# fda.net
KiCad netlist of a schematic drawn in Altium Designer
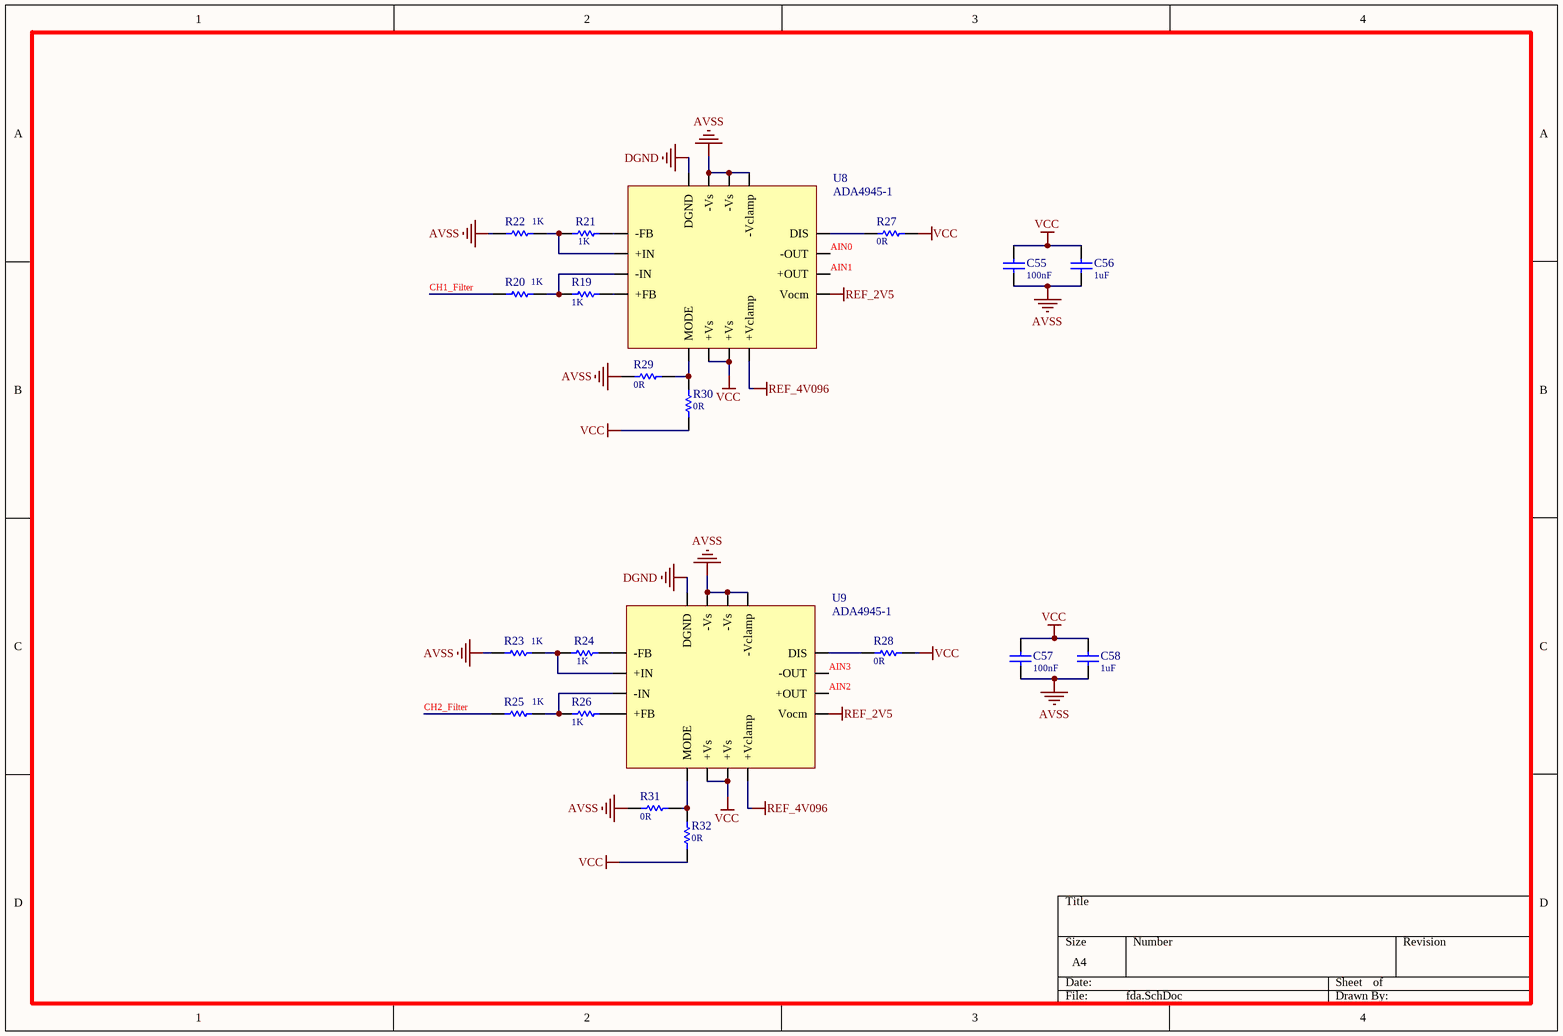
[diagram p0: fda.SchDoc]

(export (version "E")
  (design (tool "Eeschema 10.0.6"))
  (components
    (comp (ref "C55")
      (value "100nF")
      (footprint "C0603-L")
      (description "贴片瓷片电容")
      (fields (field (name "Comment") "Cap-S"))
      (libsource (lib "XuZhe") (part "Cap-S"))
    )
    (comp (ref "C56")
      (value "1uF")
      (footprint "C0603-L")
      (description "贴片瓷片电容")
      (fields (field (name "Comment") "Cap-S"))
      (libsource (lib "XuZhe") (part "Cap-S"))
    )
    (comp (ref "C57")
      (value "100nF")
      (footprint "C0603-L")
      (description "贴片瓷片电容")
      (fields (field (name "Comment") "Cap-S"))
      (libsource (lib "XuZhe") (part "Cap-S"))
    )
    (comp (ref "C58")
      (value "1uF")
      (footprint "C0603-L")
      (description "贴片瓷片电容")
      (fields (field (name "Comment") "Cap-S"))
      (libsource (lib "XuZhe") (part "Cap-S"))
    )
    (comp (ref "R19")
      (value "1K")
      (footprint "R0603-L")
      (description "贴片电阻")
      (fields (field (name "Comment") "R"))
      (libsource (lib "XuZhe") (part "Res"))
    )
    (comp (ref "R20")
      (value "1K")
      (footprint "R0603-L")
      (description "贴片电阻")
      (fields (field (name "Comment") "R"))
      (libsource (lib "XuZhe") (part "Res"))
    )
    (comp (ref "R21")
      (value "1K")
      (footprint "R0603-L")
      (description "贴片电阻")
      (fields (field (name "Comment") "R"))
      (libsource (lib "XuZhe") (part "Res"))
    )
    (comp (ref "R22")
      (value "1K")
      (footprint "R0603-L")
      (description "贴片电阻")
      (fields (field (name "Comment") "R"))
      (libsource (lib "XuZhe") (part "Res"))
    )
    (comp (ref "R23")
      (value "1K")
      (footprint "R0603-L")
      (description "贴片电阻")
      (fields (field (name "Comment") "R"))
      (libsource (lib "XuZhe") (part "Res"))
    )
    (comp (ref "R24")
      (value "1K")
      (footprint "R0603-L")
      (description "贴片电阻")
      (fields (field (name "Comment") "R"))
      (libsource (lib "XuZhe") (part "Res"))
    )
    (comp (ref "R25")
      (value "1K")
      (footprint "R0603-L")
      (description "贴片电阻")
      (fields (field (name "Comment") "R"))
      (libsource (lib "XuZhe") (part "Res"))
    )
    (comp (ref "R26")
      (value "1K")
      (footprint "R0603-L")
      (description "贴片电阻")
      (fields (field (name "Comment") "R"))
      (libsource (lib "XuZhe") (part "Res"))
    )
    (comp (ref "R27")
      (value "0R")
      (footprint "R0603-L")
      (description "贴片电阻")
      (fields (field (name "Comment") "R"))
      (libsource (lib "XuZhe") (part "Res"))
    )
    (comp (ref "R28")
      (value "0R")
      (footprint "R0603-L")
      (description "贴片电阻")
      (fields (field (name "Comment") "R"))
      (libsource (lib "XuZhe") (part "Res"))
    )
    (comp (ref "R29")
      (value "0R")
      (footprint "R0603-L")
      (description "贴片电阻")
      (fields (field (name "Comment") "R"))
      (libsource (lib "XuZhe") (part "Res"))
    )
    (comp (ref "R30")
      (value "0R")
      (footprint "R0603-L")
      (description "贴片电阻")
      (fields (field (name "Comment") "R"))
      (libsource (lib "XuZhe") (part "Res"))
    )
    (comp (ref "R31")
      (value "0R")
      (footprint "R0603-L")
      (description "贴片电阻")
      (fields (field (name "Comment") "R"))
      (libsource (lib "XuZhe") (part "Res"))
    )
    (comp (ref "R32")
      (value "0R")
      (footprint "R0603-L")
      (description "贴片电阻")
      (fields (field (name "Comment") "R"))
      (libsource (lib "XuZhe") (part "Res"))
    )
    (comp (ref "U8")
      (value "ADA4945-1")
      (footprint "CP_16_22")
      (libsource (lib "ADA4945-1") (part "ADA4945-1"))
    )
    (comp (ref "U9")
      (value "ADA4945-1")
      (footprint "CP_16_22")
      (libsource (lib "ADA4945-1") (part "ADA4945-1"))
    )
  )
  (nets
    (net (code "1") (name "/AIN0") (class "Default")
      (node (ref "U8") (pin "11") (pinfunction "-OUT_11") (pintype "passive"))
    )
    (net (code "2") (name "/AIN1") (class "Default")
      (node (ref "U8") (pin "10") (pinfunction "+OUT_10") (pintype "passive"))
    )
    (net (code "3") (name "/AIN2") (class "Default")
      (node (ref "U9") (pin "10") (pinfunction "+OUT_10") (pintype "passive"))
    )
    (net (code "4") (name "/AIN3") (class "Default")
      (node (ref "U9") (pin "11") (pinfunction "-OUT_11") (pintype "passive"))
    )
    (net (code "5") (name "/CH1_Filter") (class "Default")
      (node (ref "R20") (pin "1") (pinfunction "1_1") (pintype "passive"))
    )
    (net (code "6") (name "/CH2_Filter") (class "Default")
      (node (ref "R25") (pin "1") (pinfunction "1_1") (pintype "passive"))
    )
    (net (code "7") (name "AVSS") (class "Default")
      (node (ref "C55") (pin "1") (pinfunction "1_1") (pintype "passive"))
      (node (ref "C56") (pin "1") (pinfunction "1_1") (pintype "passive"))
      (node (ref "C57") (pin "1") (pinfunction "1_1") (pintype "passive"))
      (node (ref "C58") (pin "1") (pinfunction "1_1") (pintype "passive"))
      (node (ref "R22") (pin "1") (pinfunction "1_1") (pintype "passive"))
      (node (ref "R23") (pin "1") (pinfunction "1_1") (pintype "passive"))
      (node (ref "R29") (pin "2") (pinfunction "2_2") (pintype "passive"))
      (node (ref "R31") (pin "2") (pinfunction "2_2") (pintype "passive"))
      (node (ref "U8") (pin "13") (pinfunction "-Vclamp_13") (pintype "passive"))
      (node (ref "U8") (pin "14") (pinfunction "-Vs_14") (pintype "passive"))
      (node (ref "U8") (pin "15") (pinfunction "-Vs_15") (pintype "passive"))
      (node (ref "U9") (pin "13") (pinfunction "-Vclamp_13") (pintype "passive"))
      (node (ref "U9") (pin "14") (pinfunction "-Vs_14") (pintype "passive"))
      (node (ref "U9") (pin "15") (pinfunction "-Vs_15") (pintype "passive"))
    )
    (net (code "8") (name "DGND") (class "Default")
      (node (ref "U8") (pin "16") (pinfunction "DGND_16") (pintype "passive"))
      (node (ref "U9") (pin "16") (pinfunction "DGND_16") (pintype "passive"))
    )
    (net (code "9") (name "Net-(U8-+FB)") (class "Default")
      (node (ref "R19") (pin "2") (pinfunction "2_2") (pintype "passive"))
      (node (ref "U8") (pin "4") (pinfunction "+FB_4") (pintype "passive"))
    )
    (net (code "10") (name "Net-(U8-+IN)") (class "Default")
      (node (ref "R21") (pin "1") (pinfunction "1_1") (pintype "passive"))
      (node (ref "R22") (pin "2") (pinfunction "2_2") (pintype "passive"))
      (node (ref "U8") (pin "2") (pinfunction "+IN_2") (pintype "passive"))
    )
    (net (code "11") (name "Net-(U8--FB)") (class "Default")
      (node (ref "R21") (pin "2") (pinfunction "2_2") (pintype "passive"))
      (node (ref "U8") (pin "1") (pinfunction "-FB_1") (pintype "passive"))
    )
    (net (code "12") (name "Net-(U8--IN)") (class "Default")
      (node (ref "R19") (pin "1") (pinfunction "1_1") (pintype "passive"))
      (node (ref "R20") (pin "2") (pinfunction "2_2") (pintype "passive"))
      (node (ref "U8") (pin "3") (pinfunction "-IN_3") (pintype "passive"))
    )
    (net (code "13") (name "Net-(U8-DIS)") (class "Default")
      (node (ref "R27") (pin "1") (pinfunction "1_1") (pintype "passive"))
      (node (ref "U8") (pin "12") (pinfunction "DIS_12") (pintype "passive"))
    )
    (net (code "14") (name "Net-(U8-MODE)") (class "Default")
      (node (ref "R29") (pin "1") (pinfunction "1_1") (pintype "passive"))
      (node (ref "R30") (pin "1") (pinfunction "1_1") (pintype "passive"))
      (node (ref "U8") (pin "5") (pinfunction "MODE_5") (pintype "passive"))
    )
    (net (code "15") (name "Net-(U9-+FB)") (class "Default")
      (node (ref "R26") (pin "2") (pinfunction "2_2") (pintype "passive"))
      (node (ref "U9") (pin "4") (pinfunction "+FB_4") (pintype "passive"))
    )
    (net (code "16") (name "Net-(U9-+IN)") (class "Default")
      (node (ref "R23") (pin "2") (pinfunction "2_2") (pintype "passive"))
      (node (ref "R24") (pin "1") (pinfunction "1_1") (pintype "passive"))
      (node (ref "U9") (pin "2") (pinfunction "+IN_2") (pintype "passive"))
    )
    (net (code "17") (name "Net-(U9--FB)") (class "Default")
      (node (ref "R24") (pin "2") (pinfunction "2_2") (pintype "passive"))
      (node (ref "U9") (pin "1") (pinfunction "-FB_1") (pintype "passive"))
    )
    (net (code "18") (name "Net-(U9--IN)") (class "Default")
      (node (ref "R25") (pin "2") (pinfunction "2_2") (pintype "passive"))
      (node (ref "R26") (pin "1") (pinfunction "1_1") (pintype "passive"))
      (node (ref "U9") (pin "3") (pinfunction "-IN_3") (pintype "passive"))
    )
    (net (code "19") (name "Net-(U9-DIS)") (class "Default")
      (node (ref "R28") (pin "1") (pinfunction "1_1") (pintype "passive"))
      (node (ref "U9") (pin "12") (pinfunction "DIS_12") (pintype "passive"))
    )
    (net (code "20") (name "Net-(U9-MODE)") (class "Default")
      (node (ref "R31") (pin "1") (pinfunction "1_1") (pintype "passive"))
      (node (ref "R32") (pin "1") (pinfunction "1_1") (pintype "passive"))
      (node (ref "U9") (pin "5") (pinfunction "MODE_5") (pintype "passive"))
    )
    (net (code "21") (name "REF_2V5") (class "Default")
      (node (ref "U8") (pin "9") (pinfunction "Vocm_9") (pintype "passive"))
      (node (ref "U9") (pin "9") (pinfunction "Vocm_9") (pintype "passive"))
    )
    (net (code "22") (name "REF_4V096") (class "Default")
      (node (ref "U8") (pin "8") (pinfunction "+Vclamp_8") (pintype "passive"))
      (node (ref "U9") (pin "8") (pinfunction "+Vclamp_8") (pintype "passive"))
    )
    (net (code "23") (name "VCC") (class "Default")
      (node (ref "C55") (pin "2") (pinfunction "2_2") (pintype "passive"))
      (node (ref "C56") (pin "2") (pinfunction "2_2") (pintype "passive"))
      (node (ref "C57") (pin "2") (pinfunction "2_2") (pintype "passive"))
      (node (ref "C58") (pin "2") (pinfunction "2_2") (pintype "passive"))
      (node (ref "R27") (pin "2") (pinfunction "2_2") (pintype "passive"))
      (node (ref "R28") (pin "2") (pinfunction "2_2") (pintype "passive"))
      (node (ref "R30") (pin "2") (pinfunction "2_2") (pintype "passive"))
      (node (ref "R32") (pin "2") (pinfunction "2_2") (pintype "passive"))
      (node (ref "U8") (pin "6") (pinfunction "+Vs_6") (pintype "passive"))
      (node (ref "U8") (pin "7") (pinfunction "+Vs_7") (pintype "passive"))
      (node (ref "U9") (pin "6") (pinfunction "+Vs_6") (pintype "passive"))
      (node (ref "U9") (pin "7") (pinfunction "+Vs_7") (pintype "passive"))
    )
  )
)
